# USB3_Connector.net
KiCad netlist of a schematic drawn in Altium Designer
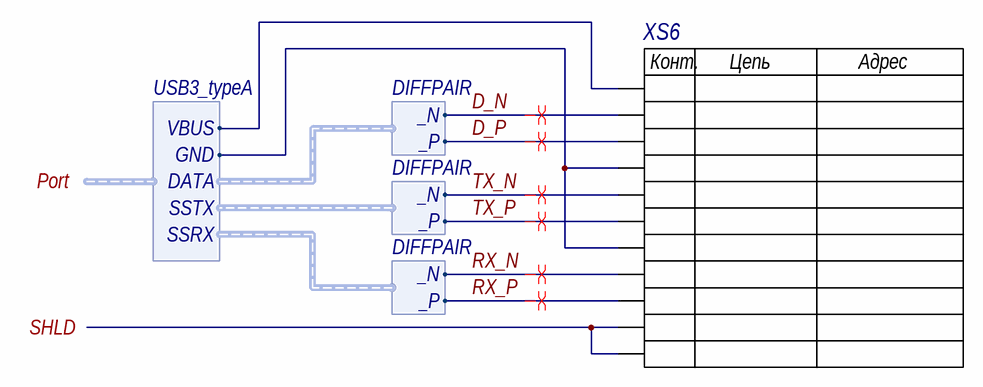
[diagram p0: USB3 Connector.SchDoc]

(export (version "E")
  (design (tool "Eeschema 10.0.6"))
  (components
    (comp (ref "XS6")
      (value "10117835")
      (footprint "FCI-10117835_V")
      (libsource (lib "MiniPC DB") (part "USB3A"))
    )
  )
  (nets
    (net (code "3") (name "/D_N") (class "Default")
      (node (ref "XS6") (pin "2") (pinfunction "D-_2") (pintype "passive"))
    )
    (net (code "4") (name "/D_P") (class "Default")
      (node (ref "XS6") (pin "3") (pinfunction "D+_3") (pintype "passive"))
    )
    (net (code "6") (name "/RX_N") (class "Default")
      (node (ref "XS6") (pin "8") (pinfunction "STDA_SSRX-_8") (pintype "passive"))
    )
    (net (code "7") (name "/RX_P") (class "Default")
      (node (ref "XS6") (pin "9") (pinfunction "STDA_SSRX+_9") (pintype "passive"))
    )
    (net (code "8") (name "/SHLD") (class "Default")
      (node (ref "XS6") (pin "10") (pinfunction "SHLD1_10") (pintype "passive"))
      (node (ref "XS6") (pin "11") (pinfunction "SHLD2_11") (pintype "passive"))
    )
    (net (code "9") (name "/TX_N") (class "Default")
      (node (ref "XS6") (pin "5") (pinfunction "STDA_SSTX-_5") (pintype "passive"))
    )
    (net (code "10") (name "/TX_P") (class "Default")
      (node (ref "XS6") (pin "6") (pinfunction "STDA_SSTX+_6") (pintype "passive"))
    )
    (net (code "12") (name "Net-(XS6-GND)") (class "Default")
      (node (ref "XS6") (pin "4") (pinfunction "GND_4") (pintype "passive"))
      (node (ref "XS6") (pin "7") (pinfunction "GND-DRAIN_7") (pintype "passive"))
    )
    (net (code "13") (name "unconnected-(XS6-VBUS-Pad1)") (class "Default")
      (node (ref "XS6") (pin "1") (pinfunction "VBUS_1") (pintype "passive"))
    )
  )
)
